# linefollower.net
KiCad netlist of a schematic drawn in EAGLE
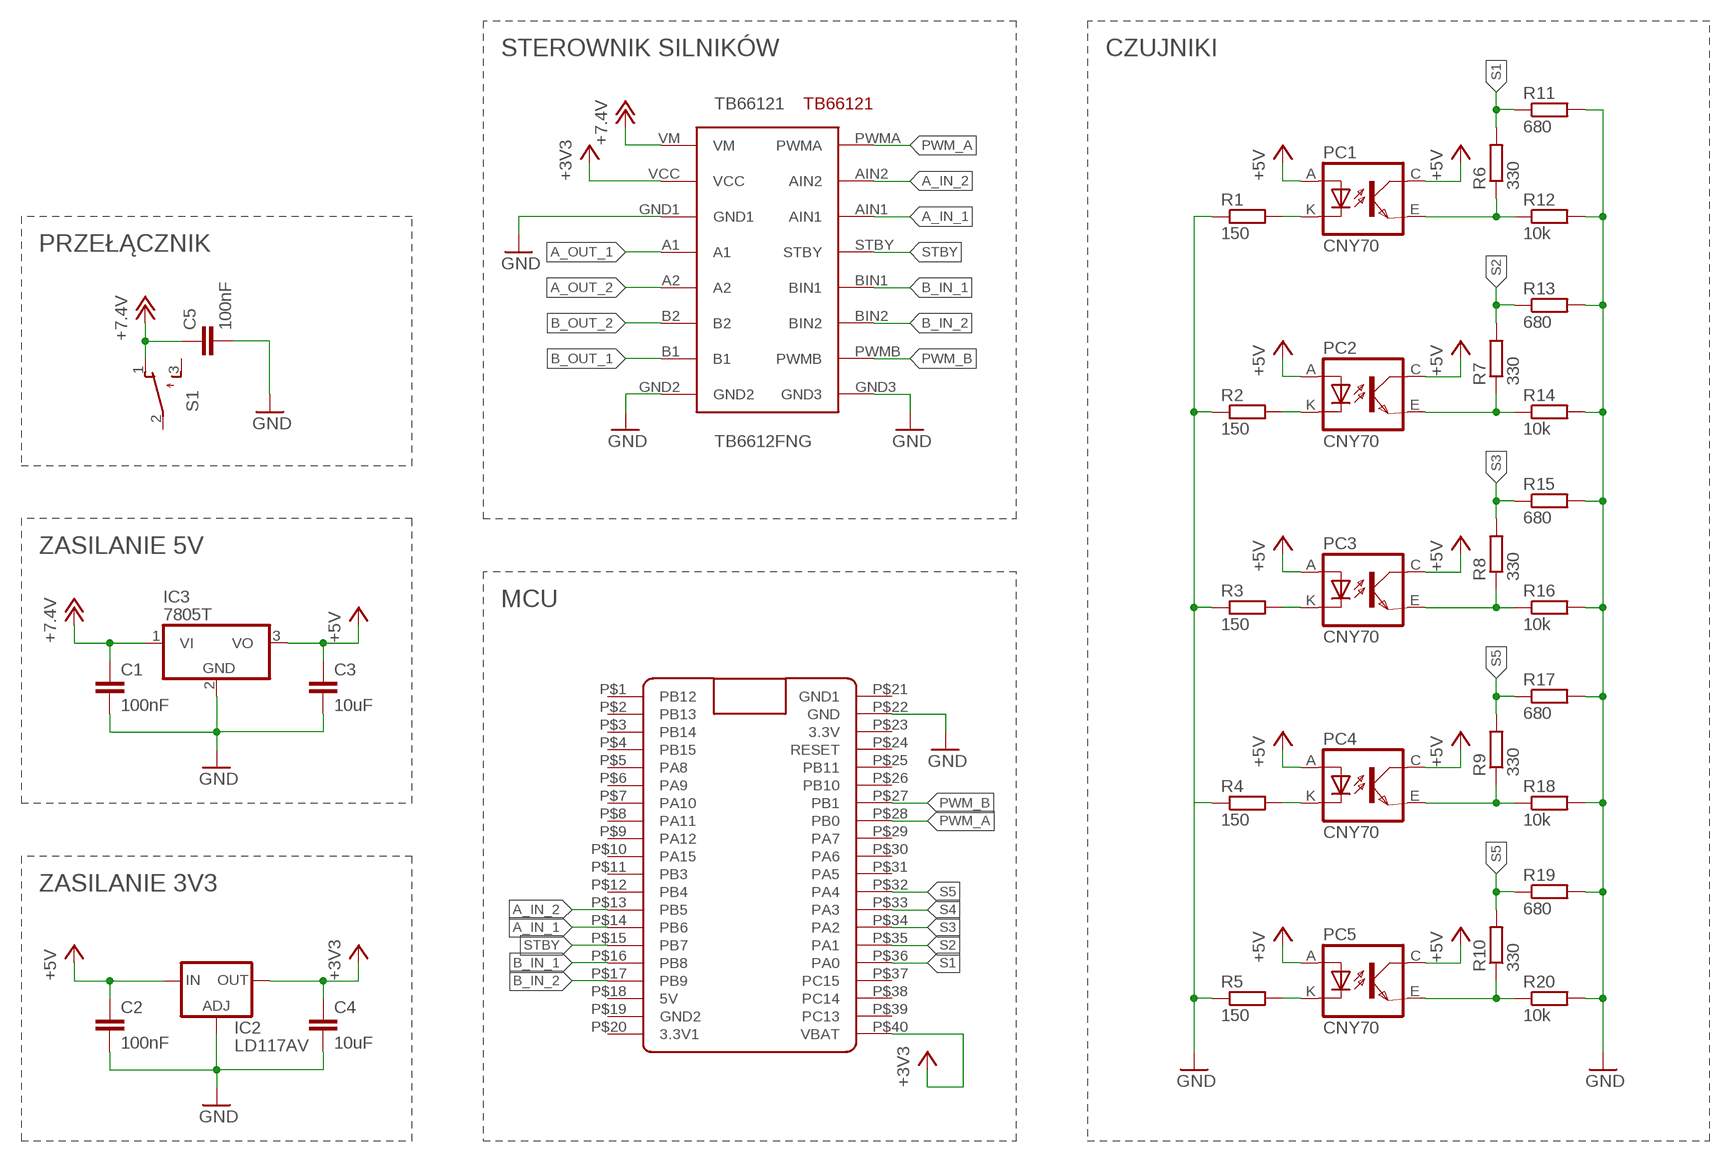
[diagram p0: schematic, sheet 1]

(export (version "E")
  (design (tool "Eeschema 10.0.6"))
  (components
    (comp (ref "C1")
      (value "100nF")
      (footprint "eagle-import:C025-024X044")
      (libsource (lib "eagle-import") (part "C-EU025-024X044"))
    )
    (comp (ref "C2")
      (value "100nF")
      (footprint "eagle-import:C025-024X044")
      (libsource (lib "eagle-import") (part "C-EU025-024X044"))
    )
    (comp (ref "C3")
      (value "10uF")
      (footprint "eagle-import:C025-024X044")
      (libsource (lib "eagle-import") (part "C-EU025-024X044"))
    )
    (comp (ref "C4")
      (value "10uF")
      (footprint "eagle-import:C025-024X044")
      (libsource (lib "eagle-import") (part "C-EU025-024X044"))
    )
    (comp (ref "C5")
      (value "100nF")
      (footprint "eagle-import:C025-024X044")
      (libsource (lib "eagle-import") (part "C-EU025-024X044"))
    )
    (comp (ref "IC2")
      (value "LD117AV")
      (footprint "eagle-import:TO220L1")
      (libsource (lib "eagle-import") (part "LD117A?V"))
    )
    (comp (ref "IC3")
      (value "7805T")
      (footprint "eagle-import:TO220H")
      (libsource (lib "eagle-import") (part "78T05"))
    )
    (comp (ref "PC1")
      (value "CNY70")
      (footprint "eagle-import:4")
      (libsource (lib "eagle-import") (part "CNY70"))
    )
    (comp (ref "PC2")
      (value "CNY70")
      (footprint "eagle-import:4")
      (libsource (lib "eagle-import") (part "CNY70"))
    )
    (comp (ref "PC3")
      (value "CNY70")
      (footprint "eagle-import:4")
      (libsource (lib "eagle-import") (part "CNY70"))
    )
    (comp (ref "PC4")
      (value "CNY70")
      (footprint "eagle-import:4")
      (libsource (lib "eagle-import") (part "CNY70"))
    )
    (comp (ref "PC5")
      (value "CNY70")
      (footprint "eagle-import:4")
      (libsource (lib "eagle-import") (part "CNY70"))
    )
    (comp (ref "R1")
      (value "150")
      (footprint "eagle-import:0204_5")
      (libsource (lib "eagle-import") (part "R-EU_0204/5"))
    )
    (comp (ref "R2")
      (value "150")
      (footprint "eagle-import:0204_5")
      (libsource (lib "eagle-import") (part "R-EU_0204/5"))
    )
    (comp (ref "R3")
      (value "150")
      (footprint "eagle-import:0204_5")
      (libsource (lib "eagle-import") (part "R-EU_0204/5"))
    )
    (comp (ref "R4")
      (value "150")
      (footprint "eagle-import:0204_5")
      (libsource (lib "eagle-import") (part "R-EU_0204/5"))
    )
    (comp (ref "R5")
      (value "150")
      (footprint "eagle-import:0204_5")
      (libsource (lib "eagle-import") (part "R-EU_0204/5"))
    )
    (comp (ref "R6")
      (value "330")
      (footprint "eagle-import:0204_5")
      (libsource (lib "eagle-import") (part "R-EU_0204/5"))
    )
    (comp (ref "R7")
      (value "330")
      (footprint "eagle-import:0204_5")
      (libsource (lib "eagle-import") (part "R-EU_0204/5"))
    )
    (comp (ref "R8")
      (value "330")
      (footprint "eagle-import:0204_5")
      (libsource (lib "eagle-import") (part "R-EU_0204/5"))
    )
    (comp (ref "R9")
      (value "330")
      (footprint "eagle-import:0204_5")
      (libsource (lib "eagle-import") (part "R-EU_0204/5"))
    )
    (comp (ref "R10")
      (value "330")
      (footprint "eagle-import:0204_5")
      (libsource (lib "eagle-import") (part "R-EU_0204/5"))
    )
    (comp (ref "R11")
      (value "680")
      (footprint "eagle-import:0204_5")
      (libsource (lib "eagle-import") (part "R-EU_0204/5"))
    )
    (comp (ref "R12")
      (value "10k")
      (footprint "eagle-import:0204_5")
      (libsource (lib "eagle-import") (part "R-EU_0204/5"))
    )
    (comp (ref "R13")
      (value "680")
      (footprint "eagle-import:0204_5")
      (libsource (lib "eagle-import") (part "R-EU_0204/5"))
    )
    (comp (ref "R14")
      (value "10k")
      (footprint "eagle-import:0204_5")
      (libsource (lib "eagle-import") (part "R-EU_0204/5"))
    )
    (comp (ref "R15")
      (value "680")
      (footprint "eagle-import:0204_5")
      (libsource (lib "eagle-import") (part "R-EU_0204/5"))
    )
    (comp (ref "R16")
      (value "10k")
      (footprint "eagle-import:0204_5")
      (libsource (lib "eagle-import") (part "R-EU_0204/5"))
    )
    (comp (ref "R17")
      (value "680")
      (footprint "eagle-import:0204_5")
      (libsource (lib "eagle-import") (part "R-EU_0204/5"))
    )
    (comp (ref "R18")
      (value "10k")
      (footprint "eagle-import:0204_5")
      (libsource (lib "eagle-import") (part "R-EU_0204/5"))
    )
    (comp (ref "R19")
      (value "680")
      (footprint "eagle-import:0204_5")
      (libsource (lib "eagle-import") (part "R-EU_0204/5"))
    )
    (comp (ref "R20")
      (value "10k")
      (footprint "eagle-import:0204_5")
      (libsource (lib "eagle-import") (part "R-EU_0204/5"))
    )
    (comp (ref "S1")
      (value "TL32PO")
      (footprint "eagle-import:TL3XPO")
      (libsource (lib "eagle-import") (part "TL32PO"))
    )
    (comp (ref "ST1")
      (value "BLUE_PILL")
      (footprint "eagle-import:BLUE_PILL")
      (libsource (lib "eagle-import") (part "BLUE_PILL"))
    )
    (comp (ref "TB66121")
      (value "TB6612FNG")
      (footprint "eagle-import:TB6612FNG")
      (libsource (lib "eagle-import") (part "TB6612FNG"))
    )
  )
  (nets
    (net (code "1") (name "+3V3") (class "Default")
      (node (ref "C4") (pin "1") (pinfunction "1_1") (pintype "passive"))
      (node (ref "IC2") (pin "2") (pinfunction "OUT_2") (pintype "passive"))
      (node (ref "ST1") (pin "P$40") (pinfunction "VBAT_P$40") (pintype "bidirectional"))
      (node (ref "TB66121") (pin "VCC") (pinfunction "VCC_VCC") (pintype "bidirectional"))
    )
    (net (code "2") (name "+5V") (class "Default")
      (node (ref "C2") (pin "1") (pinfunction "1_1") (pintype "passive"))
      (node (ref "C3") (pin "1") (pinfunction "1_1") (pintype "passive"))
      (node (ref "IC2") (pin "3") (pinfunction "IN_3") (pintype "input"))
      (node (ref "IC3") (pin "3") (pinfunction "VO_3") (pintype "passive"))
      (node (ref "PC1") (pin "A") (pinfunction "A_A") (pintype "passive"))
      (node (ref "PC1") (pin "C") (pinfunction "COL_C") (pintype "passive"))
      (node (ref "PC2") (pin "A") (pinfunction "A_A") (pintype "passive"))
      (node (ref "PC2") (pin "C") (pinfunction "COL_C") (pintype "passive"))
      (node (ref "PC3") (pin "A") (pinfunction "A_A") (pintype "passive"))
      (node (ref "PC3") (pin "C") (pinfunction "COL_C") (pintype "passive"))
      (node (ref "PC4") (pin "A") (pinfunction "A_A") (pintype "passive"))
      (node (ref "PC4") (pin "C") (pinfunction "COL_C") (pintype "passive"))
      (node (ref "PC5") (pin "A") (pinfunction "A_A") (pintype "passive"))
      (node (ref "PC5") (pin "C") (pinfunction "COL_C") (pintype "passive"))
    )
    (net (code "3") (name "+7.4V") (class "Default")
      (node (ref "C1") (pin "1") (pinfunction "1_1") (pintype "passive"))
      (node (ref "C5") (pin "1") (pinfunction "1_1") (pintype "passive"))
      (node (ref "IC3") (pin "1") (pinfunction "VI_1") (pintype "input"))
      (node (ref "S1") (pin "1") (pinfunction "O_1") (pintype "passive"))
      (node (ref "TB66121") (pin "VM") (pinfunction "VM_VM") (pintype "bidirectional"))
    )
    (net (code "4") (name "/GND1") (class "Default")
      (node (ref "ST1") (pin "P$21") (pinfunction "GND1_P$21") (pintype "power_in"))
    )
    (net (code "5") (name "A_IN_1") (class "Default")
      (node (ref "ST1") (pin "P$14") (pinfunction "PB6_P$14") (pintype "bidirectional"))
      (node (ref "TB66121") (pin "AIN1") (pinfunction "AIN1_AIN1") (pintype "bidirectional"))
    )
    (net (code "6") (name "A_IN_2") (class "Default")
      (node (ref "ST1") (pin "P$13") (pinfunction "PB5_P$13") (pintype "bidirectional"))
      (node (ref "TB66121") (pin "AIN2") (pinfunction "AIN2_AIN2") (pintype "bidirectional"))
    )
    (net (code "7") (name "A_OUT_1") (class "Default")
      (node (ref "TB66121") (pin "A1") (pinfunction "A1_A1") (pintype "bidirectional"))
    )
    (net (code "8") (name "A_OUT_2") (class "Default")
      (node (ref "TB66121") (pin "A2") (pinfunction "A2_A2") (pintype "bidirectional"))
    )
    (net (code "9") (name "B_IN_1") (class "Default")
      (node (ref "ST1") (pin "P$16") (pinfunction "PB8_P$16") (pintype "bidirectional"))
      (node (ref "TB66121") (pin "BIN1") (pinfunction "BIN1_BIN1") (pintype "bidirectional"))
    )
    (net (code "10") (name "B_IN_2") (class "Default")
      (node (ref "ST1") (pin "P$17") (pinfunction "PB9_P$17") (pintype "bidirectional"))
      (node (ref "TB66121") (pin "BIN2") (pinfunction "BIN2_BIN2") (pintype "bidirectional"))
    )
    (net (code "11") (name "B_OUT_1") (class "Default")
      (node (ref "TB66121") (pin "B1") (pinfunction "B1_B1") (pintype "bidirectional"))
    )
    (net (code "12") (name "B_OUT_2") (class "Default")
      (node (ref "TB66121") (pin "B2") (pinfunction "B2_B2") (pintype "bidirectional"))
    )
    (net (code "13") (name "GND") (class "Default")
      (node (ref "C1") (pin "2") (pinfunction "2_2") (pintype "passive"))
      (node (ref "C2") (pin "2") (pinfunction "2_2") (pintype "passive"))
      (node (ref "C3") (pin "2") (pinfunction "2_2") (pintype "passive"))
      (node (ref "C4") (pin "2") (pinfunction "2_2") (pintype "passive"))
      (node (ref "C5") (pin "2") (pinfunction "2_2") (pintype "passive"))
      (node (ref "IC2") (pin "1") (pinfunction "ADJ_1") (pintype "input"))
      (node (ref "IC3") (pin "2") (pinfunction "GND_2") (pintype "passive"))
      (node (ref "R1") (pin "1") (pinfunction "1_1") (pintype "passive"))
      (node (ref "R11") (pin "2") (pinfunction "2_2") (pintype "passive"))
      (node (ref "R12") (pin "2") (pinfunction "2_2") (pintype "passive"))
      (node (ref "R13") (pin "2") (pinfunction "2_2") (pintype "passive"))
      (node (ref "R14") (pin "2") (pinfunction "2_2") (pintype "passive"))
      (node (ref "R15") (pin "2") (pinfunction "2_2") (pintype "passive"))
      (node (ref "R16") (pin "2") (pinfunction "2_2") (pintype "passive"))
      (node (ref "R17") (pin "2") (pinfunction "2_2") (pintype "passive"))
      (node (ref "R18") (pin "2") (pinfunction "2_2") (pintype "passive"))
      (node (ref "R19") (pin "2") (pinfunction "2_2") (pintype "passive"))
      (node (ref "R2") (pin "1") (pinfunction "1_1") (pintype "passive"))
      (node (ref "R20") (pin "2") (pinfunction "2_2") (pintype "passive"))
      (node (ref "R3") (pin "1") (pinfunction "1_1") (pintype "passive"))
      (node (ref "R5") (pin "1") (pinfunction "1_1") (pintype "passive"))
      (node (ref "ST1") (pin "P$22") (pinfunction "GND_P$22") (pintype "bidirectional"))
      (node (ref "TB66121") (pin "GND1") (pinfunction "GND1_GND1") (pintype "bidirectional"))
      (node (ref "TB66121") (pin "GND2") (pinfunction "GND2_GND2") (pintype "bidirectional"))
      (node (ref "TB66121") (pin "GND3") (pinfunction "GND3_GND3") (pintype "bidirectional"))
    )
    (net (code "14") (name "Net-(PC1-C)") (class "Default")
      (node (ref "PC1") (pin "K") (pinfunction "C_K") (pintype "passive"))
      (node (ref "R1") (pin "2") (pinfunction "2_2") (pintype "passive"))
    )
    (net (code "15") (name "Net-(PC2-C)") (class "Default")
      (node (ref "PC2") (pin "K") (pinfunction "C_K") (pintype "passive"))
      (node (ref "R2") (pin "2") (pinfunction "2_2") (pintype "passive"))
    )
    (net (code "16") (name "Net-(PC3-C)") (class "Default")
      (node (ref "PC3") (pin "K") (pinfunction "C_K") (pintype "passive"))
      (node (ref "R3") (pin "2") (pinfunction "2_2") (pintype "passive"))
    )
    (net (code "17") (name "Net-(PC4-C)") (class "Default")
      (node (ref "PC4") (pin "K") (pinfunction "C_K") (pintype "passive"))
      (node (ref "R4") (pin "2") (pinfunction "2_2") (pintype "passive"))
    )
    (net (code "18") (name "Net-(PC5-C)") (class "Default")
      (node (ref "PC5") (pin "K") (pinfunction "C_K") (pintype "passive"))
      (node (ref "R5") (pin "2") (pinfunction "2_2") (pintype "passive"))
    )
    (net (code "19") (name "PWM_A") (class "Default")
      (node (ref "ST1") (pin "P$28") (pinfunction "PB0_P$28") (pintype "bidirectional"))
      (node (ref "TB66121") (pin "PWMA") (pinfunction "PWMA_PWMA") (pintype "bidirectional"))
    )
    (net (code "20") (name "PWM_B") (class "Default")
      (node (ref "ST1") (pin "P$27") (pinfunction "PB1_P$27") (pintype "bidirectional"))
      (node (ref "TB66121") (pin "PWMB") (pinfunction "PWMB_PWMB") (pintype "bidirectional"))
    )
    (net (code "21") (name "S1") (class "Default")
      (node (ref "PC1") (pin "E") (pinfunction "EMI_E") (pintype "passive"))
      (node (ref "R11") (pin "1") (pinfunction "1_1") (pintype "passive"))
      (node (ref "R12") (pin "1") (pinfunction "1_1") (pintype "passive"))
      (node (ref "R6") (pin "1") (pinfunction "1_1") (pintype "passive"))
      (node (ref "R6") (pin "2") (pinfunction "2_2") (pintype "passive"))
      (node (ref "ST1") (pin "P$36") (pinfunction "PA0_P$36") (pintype "bidirectional"))
    )
    (net (code "22") (name "S2") (class "Default")
      (node (ref "PC2") (pin "E") (pinfunction "EMI_E") (pintype "passive"))
      (node (ref "R13") (pin "1") (pinfunction "1_1") (pintype "passive"))
      (node (ref "R14") (pin "1") (pinfunction "1_1") (pintype "passive"))
      (node (ref "R7") (pin "1") (pinfunction "1_1") (pintype "passive"))
      (node (ref "R7") (pin "2") (pinfunction "2_2") (pintype "passive"))
      (node (ref "ST1") (pin "P$35") (pinfunction "PA1_P$35") (pintype "bidirectional"))
    )
    (net (code "23") (name "S3") (class "Default")
      (node (ref "PC3") (pin "E") (pinfunction "EMI_E") (pintype "passive"))
      (node (ref "R15") (pin "1") (pinfunction "1_1") (pintype "passive"))
      (node (ref "R16") (pin "1") (pinfunction "1_1") (pintype "passive"))
      (node (ref "R8") (pin "1") (pinfunction "1_1") (pintype "passive"))
      (node (ref "R8") (pin "2") (pinfunction "2_2") (pintype "passive"))
      (node (ref "ST1") (pin "P$34") (pinfunction "PA2_P$34") (pintype "bidirectional"))
    )
    (net (code "24") (name "S4") (class "Default")
      (node (ref "ST1") (pin "P$33") (pinfunction "PA3_P$33") (pintype "bidirectional"))
    )
    (net (code "25") (name "S5") (class "Default")
      (node (ref "PC4") (pin "E") (pinfunction "EMI_E") (pintype "passive"))
      (node (ref "PC5") (pin "E") (pinfunction "EMI_E") (pintype "passive"))
      (node (ref "R10") (pin "1") (pinfunction "1_1") (pintype "passive"))
      (node (ref "R10") (pin "2") (pinfunction "2_2") (pintype "passive"))
      (node (ref "R17") (pin "1") (pinfunction "1_1") (pintype "passive"))
      (node (ref "R18") (pin "1") (pinfunction "1_1") (pintype "passive"))
      (node (ref "R19") (pin "1") (pinfunction "1_1") (pintype "passive"))
      (node (ref "R20") (pin "1") (pinfunction "1_1") (pintype "passive"))
      (node (ref "R9") (pin "1") (pinfunction "1_1") (pintype "passive"))
      (node (ref "R9") (pin "2") (pinfunction "2_2") (pintype "passive"))
      (node (ref "ST1") (pin "P$32") (pinfunction "PA4_P$32") (pintype "bidirectional"))
    )
    (net (code "26") (name "STBY") (class "Default")
      (node (ref "ST1") (pin "P$15") (pinfunction "PB7_P$15") (pintype "bidirectional"))
      (node (ref "TB66121") (pin "STBY") (pinfunction "STBY_STBY") (pintype "bidirectional"))
    )
    (net (code "27") (name "unconnected-(R4-Pad1)") (class "Default")
      (node (ref "R4") (pin "1") (pinfunction "1_1") (pintype "passive"))
    )
    (net (code "28") (name "unconnected-(S1-P-Pad2)") (class "Default")
      (node (ref "S1") (pin "2") (pinfunction "P_2") (pintype "passive"))
    )
    (net (code "29") (name "unconnected-(S1-S-Pad3)") (class "Default")
      (node (ref "S1") (pin "3") (pinfunction "S_3") (pintype "passive"))
    )
    (net (code "30") (name "unconnected-(ST1-3.3V-PadP$23)") (class "Default")
      (node (ref "ST1") (pin "P$23") (pinfunction "3.3V_P$23") (pintype "bidirectional"))
    )
    (net (code "31") (name "unconnected-(ST1-3.3V1-PadP$20)") (class "Default")
      (node (ref "ST1") (pin "P$20") (pinfunction "3.3V1_P$20") (pintype "bidirectional"))
    )
    (net (code "32") (name "unconnected-(ST1-5V-PadP$18)") (class "Default")
      (node (ref "ST1") (pin "P$18") (pinfunction "5V_P$18") (pintype "bidirectional"))
    )
    (net (code "33") (name "unconnected-(ST1-GND2-PadP$19)") (class "Default")
      (node (ref "ST1") (pin "P$19") (pinfunction "GND2_P$19") (pintype "bidirectional"))
    )
    (net (code "34") (name "unconnected-(ST1-PA5-PadP$31)") (class "Default")
      (node (ref "ST1") (pin "P$31") (pinfunction "PA5_P$31") (pintype "bidirectional"))
    )
    (net (code "35") (name "unconnected-(ST1-PA6-PadP$30)") (class "Default")
      (node (ref "ST1") (pin "P$30") (pinfunction "PA6_P$30") (pintype "bidirectional"))
    )
    (net (code "36") (name "unconnected-(ST1-PA7-PadP$29)") (class "Default")
      (node (ref "ST1") (pin "P$29") (pinfunction "PA7_P$29") (pintype "bidirectional"))
    )
    (net (code "37") (name "unconnected-(ST1-PA8-PadP$5)") (class "Default")
      (node (ref "ST1") (pin "P$5") (pinfunction "PA8_P$5") (pintype "bidirectional"))
    )
    (net (code "38") (name "unconnected-(ST1-PA9-PadP$6)") (class "Default")
      (node (ref "ST1") (pin "P$6") (pinfunction "PA9_P$6") (pintype "bidirectional"))
    )
    (net (code "39") (name "unconnected-(ST1-PA10-PadP$7)") (class "Default")
      (node (ref "ST1") (pin "P$7") (pinfunction "PA10_P$7") (pintype "bidirectional"))
    )
    (net (code "40") (name "unconnected-(ST1-PA11-PadP$8)") (class "Default")
      (node (ref "ST1") (pin "P$8") (pinfunction "PA11_P$8") (pintype "bidirectional"))
    )
    (net (code "41") (name "unconnected-(ST1-PA12-PadP$9)") (class "Default")
      (node (ref "ST1") (pin "P$9") (pinfunction "PA12_P$9") (pintype "bidirectional"))
    )
    (net (code "42") (name "unconnected-(ST1-PA15-PadP$10)") (class "Default")
      (node (ref "ST1") (pin "P$10") (pinfunction "PA15_P$10") (pintype "bidirectional"))
    )
    (net (code "43") (name "unconnected-(ST1-PB3-PadP$11)") (class "Default")
      (node (ref "ST1") (pin "P$11") (pinfunction "PB3_P$11") (pintype "bidirectional"))
    )
    (net (code "44") (name "unconnected-(ST1-PB4-PadP$12)") (class "Default")
      (node (ref "ST1") (pin "P$12") (pinfunction "PB4_P$12") (pintype "bidirectional"))
    )
    (net (code "45") (name "unconnected-(ST1-PB10-PadP$26)") (class "Default")
      (node (ref "ST1") (pin "P$26") (pinfunction "PB10_P$26") (pintype "bidirectional"))
    )
    (net (code "46") (name "unconnected-(ST1-PB11-PadP$25)") (class "Default")
      (node (ref "ST1") (pin "P$25") (pinfunction "PB11_P$25") (pintype "bidirectional"))
    )
    (net (code "47") (name "unconnected-(ST1-PB12-PadP$1)") (class "Default")
      (node (ref "ST1") (pin "P$1") (pinfunction "PB12_P$1") (pintype "bidirectional"))
    )
    (net (code "48") (name "unconnected-(ST1-PB13-PadP$2)") (class "Default")
      (node (ref "ST1") (pin "P$2") (pinfunction "PB13_P$2") (pintype "bidirectional"))
    )
    (net (code "49") (name "unconnected-(ST1-PB14-PadP$3)") (class "Default")
      (node (ref "ST1") (pin "P$3") (pinfunction "PB14_P$3") (pintype "bidirectional"))
    )
    (net (code "50") (name "unconnected-(ST1-PB15-PadP$4)") (class "Default")
      (node (ref "ST1") (pin "P$4") (pinfunction "PB15_P$4") (pintype "bidirectional"))
    )
    (net (code "51") (name "unconnected-(ST1-PC13-PadP$39)") (class "Default")
      (node (ref "ST1") (pin "P$39") (pinfunction "PC13_P$39") (pintype "bidirectional"))
    )
    (net (code "52") (name "unconnected-(ST1-PC14-PadP$38)") (class "Default")
      (node (ref "ST1") (pin "P$38") (pinfunction "PC14_P$38") (pintype "bidirectional"))
    )
    (net (code "53") (name "unconnected-(ST1-PC15-PadP$37)") (class "Default")
      (node (ref "ST1") (pin "P$37") (pinfunction "PC15_P$37") (pintype "bidirectional"))
    )
    (net (code "54") (name "unconnected-(ST1-RESET-PadP$24)") (class "Default")
      (node (ref "ST1") (pin "P$24") (pinfunction "RESET_P$24") (pintype "bidirectional"))
    )
  )
)
